# PixelPusher-ethernet-extender-shield.net
KiCad netlist of a schematic drawn in EAGLE
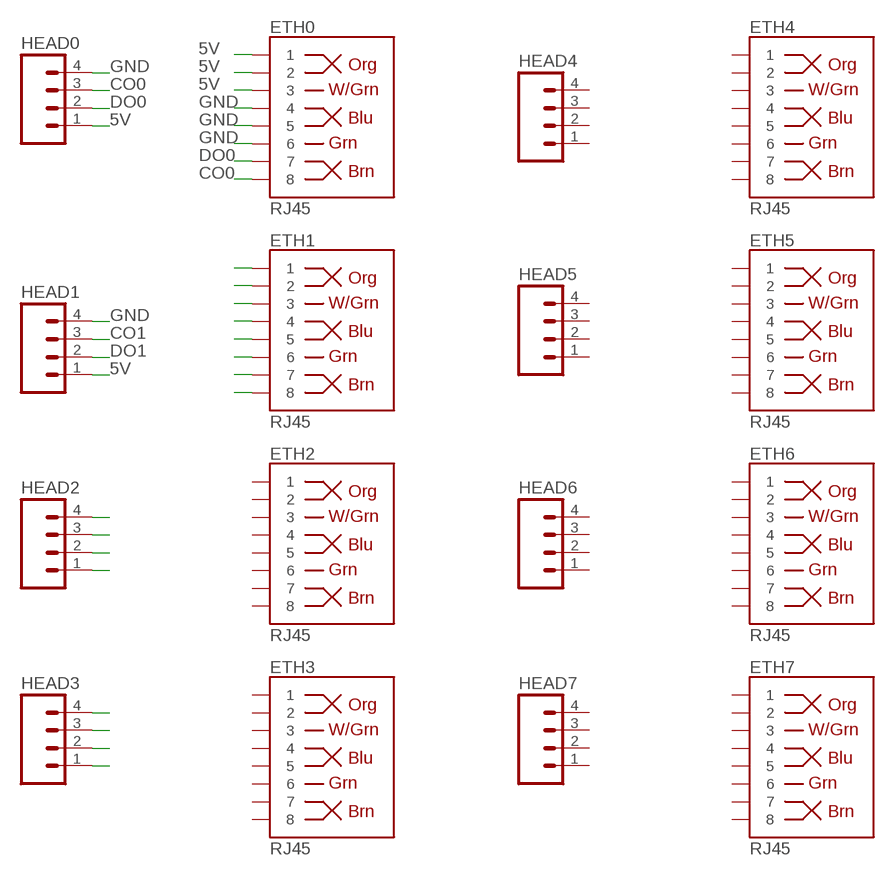
[diagram p0: schematic, sheet 1]

(export (version "E")
  (design (tool "Eeschema 10.0.6"))
  (components
    (comp (ref "ETH0")
      (value "RJ45")
      (footprint "eagle-import:RJ45-8")
      (libsource (lib "eagle-import") (part "RJ45-8PTH"))
    )
    (comp (ref "ETH1")
      (value "RJ45")
      (footprint "eagle-import:RJ45-8")
      (libsource (lib "eagle-import") (part "RJ45-8PTH"))
    )
    (comp (ref "ETH2")
      (value "RJ45")
      (footprint "eagle-import:RJ45-8")
      (libsource (lib "eagle-import") (part "RJ45-8PTH"))
    )
    (comp (ref "ETH3")
      (value "RJ45")
      (footprint "eagle-import:RJ45-8")
      (libsource (lib "eagle-import") (part "RJ45-8PTH"))
    )
    (comp (ref "ETH4")
      (value "RJ45")
      (footprint "eagle-import:RJ45-8")
      (libsource (lib "eagle-import") (part "RJ45-8PTH"))
    )
    (comp (ref "ETH5")
      (value "RJ45")
      (footprint "eagle-import:RJ45-8")
      (libsource (lib "eagle-import") (part "RJ45-8PTH"))
    )
    (comp (ref "ETH6")
      (value "RJ45")
      (footprint "eagle-import:RJ45-8")
      (libsource (lib "eagle-import") (part "RJ45-8PTH"))
    )
    (comp (ref "ETH7")
      (value "RJ45")
      (footprint "eagle-import:RJ45-8")
      (libsource (lib "eagle-import") (part "RJ45-8PTH"))
    )
    (comp (ref "HEAD0")
      (value "M04JST-PTH-VERT")
      (footprint "eagle-import:JST-4-PTH-VERT")
      (libsource (lib "eagle-import") (part "M04JST-PTH-VERT"))
    )
    (comp (ref "HEAD1")
      (value "M04JST-PTH-VERT")
      (footprint "eagle-import:JST-4-PTH-VERT")
      (libsource (lib "eagle-import") (part "M04JST-PTH-VERT"))
    )
    (comp (ref "HEAD2")
      (value "M04JST-PTH-VERT")
      (footprint "eagle-import:JST-4-PTH-VERT")
      (libsource (lib "eagle-import") (part "M04JST-PTH-VERT"))
    )
    (comp (ref "HEAD3")
      (value "M04JST-PTH-VERT")
      (footprint "eagle-import:JST-4-PTH-VERT")
      (libsource (lib "eagle-import") (part "M04JST-PTH-VERT"))
    )
    (comp (ref "HEAD4")
      (value "M04JST-PTH-VERT")
      (footprint "eagle-import:JST-4-PTH-VERT")
      (libsource (lib "eagle-import") (part "M04JST-PTH-VERT"))
    )
    (comp (ref "HEAD5")
      (value "M04JST-PTH-VERT")
      (footprint "eagle-import:JST-4-PTH-VERT")
      (libsource (lib "eagle-import") (part "M04JST-PTH-VERT"))
    )
    (comp (ref "HEAD6")
      (value "M04JST-PTH-VERT")
      (footprint "eagle-import:JST-4-PTH-VERT")
      (libsource (lib "eagle-import") (part "M04JST-PTH-VERT"))
    )
    (comp (ref "HEAD7")
      (value "M04JST-PTH-VERT")
      (footprint "eagle-import:JST-4-PTH-VERT")
      (libsource (lib "eagle-import") (part "M04JST-PTH-VERT"))
    )
  )
  (nets
    (net (code "1") (name "/5V") (class "Default")
      (node (ref "ETH0") (pin "1") (pinfunction "1_1") (pintype "bidirectional"))
      (node (ref "ETH0") (pin "2") (pinfunction "2_2") (pintype "bidirectional"))
      (node (ref "ETH0") (pin "3") (pinfunction "3_3") (pintype "bidirectional"))
      (node (ref "HEAD0") (pin "1") (pinfunction "1_1") (pintype "passive"))
      (node (ref "HEAD1") (pin "1") (pinfunction "1_1") (pintype "passive"))
    )
    (net (code "2") (name "/CO0") (class "Default")
      (node (ref "ETH0") (pin "8") (pinfunction "8_8") (pintype "bidirectional"))
      (node (ref "HEAD0") (pin "3") (pinfunction "3_3") (pintype "passive"))
    )
    (net (code "3") (name "/CO1") (class "Default")
      (node (ref "HEAD1") (pin "3") (pinfunction "3_3") (pintype "passive"))
    )
    (net (code "4") (name "/DO0") (class "Default")
      (node (ref "ETH0") (pin "7") (pinfunction "7_7") (pintype "bidirectional"))
      (node (ref "HEAD0") (pin "2") (pinfunction "2_2") (pintype "passive"))
    )
    (net (code "5") (name "/DO1") (class "Default")
      (node (ref "HEAD1") (pin "2") (pinfunction "2_2") (pintype "passive"))
    )
    (net (code "6") (name "/GND") (class "Default")
      (node (ref "ETH0") (pin "4") (pinfunction "4_4") (pintype "bidirectional"))
      (node (ref "ETH0") (pin "5") (pinfunction "5_5") (pintype "bidirectional"))
      (node (ref "ETH0") (pin "6") (pinfunction "6_6") (pintype "bidirectional"))
      (node (ref "HEAD0") (pin "4") (pinfunction "4_4") (pintype "passive"))
      (node (ref "HEAD1") (pin "4") (pinfunction "4_4") (pintype "passive"))
    )
    (net (code "7") (name "unconnected-(ETH1-Pad1)") (class "Default")
      (node (ref "ETH1") (pin "1") (pinfunction "1_1") (pintype "bidirectional"))
    )
    (net (code "8") (name "unconnected-(ETH1-Pad2)") (class "Default")
      (node (ref "ETH1") (pin "2") (pinfunction "2_2") (pintype "bidirectional"))
    )
    (net (code "9") (name "unconnected-(ETH1-Pad3)") (class "Default")
      (node (ref "ETH1") (pin "3") (pinfunction "3_3") (pintype "bidirectional"))
    )
    (net (code "10") (name "unconnected-(ETH1-Pad4)") (class "Default")
      (node (ref "ETH1") (pin "4") (pinfunction "4_4") (pintype "bidirectional"))
    )
    (net (code "11") (name "unconnected-(ETH1-Pad5)") (class "Default")
      (node (ref "ETH1") (pin "5") (pinfunction "5_5") (pintype "bidirectional"))
    )
    (net (code "12") (name "unconnected-(ETH1-Pad6)") (class "Default")
      (node (ref "ETH1") (pin "6") (pinfunction "6_6") (pintype "bidirectional"))
    )
    (net (code "13") (name "unconnected-(ETH1-Pad7)") (class "Default")
      (node (ref "ETH1") (pin "7") (pinfunction "7_7") (pintype "bidirectional"))
    )
    (net (code "14") (name "unconnected-(ETH1-Pad8)") (class "Default")
      (node (ref "ETH1") (pin "8") (pinfunction "8_8") (pintype "bidirectional"))
    )
    (net (code "15") (name "unconnected-(ETH2-Pad1)") (class "Default")
      (node (ref "ETH2") (pin "1") (pinfunction "1_1") (pintype "bidirectional"))
    )
    (net (code "16") (name "unconnected-(ETH2-Pad2)") (class "Default")
      (node (ref "ETH2") (pin "2") (pinfunction "2_2") (pintype "bidirectional"))
    )
    (net (code "17") (name "unconnected-(ETH2-Pad3)") (class "Default")
      (node (ref "ETH2") (pin "3") (pinfunction "3_3") (pintype "bidirectional"))
    )
    (net (code "18") (name "unconnected-(ETH2-Pad4)") (class "Default")
      (node (ref "ETH2") (pin "4") (pinfunction "4_4") (pintype "bidirectional"))
    )
    (net (code "19") (name "unconnected-(ETH2-Pad5)") (class "Default")
      (node (ref "ETH2") (pin "5") (pinfunction "5_5") (pintype "bidirectional"))
    )
    (net (code "20") (name "unconnected-(ETH2-Pad6)") (class "Default")
      (node (ref "ETH2") (pin "6") (pinfunction "6_6") (pintype "bidirectional"))
    )
    (net (code "21") (name "unconnected-(ETH2-Pad7)") (class "Default")
      (node (ref "ETH2") (pin "7") (pinfunction "7_7") (pintype "bidirectional"))
    )
    (net (code "22") (name "unconnected-(ETH2-Pad8)") (class "Default")
      (node (ref "ETH2") (pin "8") (pinfunction "8_8") (pintype "bidirectional"))
    )
    (net (code "23") (name "unconnected-(ETH3-Pad1)") (class "Default")
      (node (ref "ETH3") (pin "1") (pinfunction "1_1") (pintype "bidirectional"))
    )
    (net (code "24") (name "unconnected-(ETH3-Pad2)") (class "Default")
      (node (ref "ETH3") (pin "2") (pinfunction "2_2") (pintype "bidirectional"))
    )
    (net (code "25") (name "unconnected-(ETH3-Pad3)") (class "Default")
      (node (ref "ETH3") (pin "3") (pinfunction "3_3") (pintype "bidirectional"))
    )
    (net (code "26") (name "unconnected-(ETH3-Pad4)") (class "Default")
      (node (ref "ETH3") (pin "4") (pinfunction "4_4") (pintype "bidirectional"))
    )
    (net (code "27") (name "unconnected-(ETH3-Pad5)") (class "Default")
      (node (ref "ETH3") (pin "5") (pinfunction "5_5") (pintype "bidirectional"))
    )
    (net (code "28") (name "unconnected-(ETH3-Pad6)") (class "Default")
      (node (ref "ETH3") (pin "6") (pinfunction "6_6") (pintype "bidirectional"))
    )
    (net (code "29") (name "unconnected-(ETH3-Pad7)") (class "Default")
      (node (ref "ETH3") (pin "7") (pinfunction "7_7") (pintype "bidirectional"))
    )
    (net (code "30") (name "unconnected-(ETH3-Pad8)") (class "Default")
      (node (ref "ETH3") (pin "8") (pinfunction "8_8") (pintype "bidirectional"))
    )
    (net (code "31") (name "unconnected-(ETH4-Pad1)") (class "Default")
      (node (ref "ETH4") (pin "1") (pinfunction "1_1") (pintype "bidirectional"))
    )
    (net (code "32") (name "unconnected-(ETH4-Pad2)") (class "Default")
      (node (ref "ETH4") (pin "2") (pinfunction "2_2") (pintype "bidirectional"))
    )
    (net (code "33") (name "unconnected-(ETH4-Pad3)") (class "Default")
      (node (ref "ETH4") (pin "3") (pinfunction "3_3") (pintype "bidirectional"))
    )
    (net (code "34") (name "unconnected-(ETH4-Pad4)") (class "Default")
      (node (ref "ETH4") (pin "4") (pinfunction "4_4") (pintype "bidirectional"))
    )
    (net (code "35") (name "unconnected-(ETH4-Pad5)") (class "Default")
      (node (ref "ETH4") (pin "5") (pinfunction "5_5") (pintype "bidirectional"))
    )
    (net (code "36") (name "unconnected-(ETH4-Pad6)") (class "Default")
      (node (ref "ETH4") (pin "6") (pinfunction "6_6") (pintype "bidirectional"))
    )
    (net (code "37") (name "unconnected-(ETH4-Pad7)") (class "Default")
      (node (ref "ETH4") (pin "7") (pinfunction "7_7") (pintype "bidirectional"))
    )
    (net (code "38") (name "unconnected-(ETH4-Pad8)") (class "Default")
      (node (ref "ETH4") (pin "8") (pinfunction "8_8") (pintype "bidirectional"))
    )
    (net (code "39") (name "unconnected-(ETH5-Pad1)") (class "Default")
      (node (ref "ETH5") (pin "1") (pinfunction "1_1") (pintype "bidirectional"))
    )
    (net (code "40") (name "unconnected-(ETH5-Pad2)") (class "Default")
      (node (ref "ETH5") (pin "2") (pinfunction "2_2") (pintype "bidirectional"))
    )
    (net (code "41") (name "unconnected-(ETH5-Pad3)") (class "Default")
      (node (ref "ETH5") (pin "3") (pinfunction "3_3") (pintype "bidirectional"))
    )
    (net (code "42") (name "unconnected-(ETH5-Pad4)") (class "Default")
      (node (ref "ETH5") (pin "4") (pinfunction "4_4") (pintype "bidirectional"))
    )
    (net (code "43") (name "unconnected-(ETH5-Pad5)") (class "Default")
      (node (ref "ETH5") (pin "5") (pinfunction "5_5") (pintype "bidirectional"))
    )
    (net (code "44") (name "unconnected-(ETH5-Pad6)") (class "Default")
      (node (ref "ETH5") (pin "6") (pinfunction "6_6") (pintype "bidirectional"))
    )
    (net (code "45") (name "unconnected-(ETH5-Pad7)") (class "Default")
      (node (ref "ETH5") (pin "7") (pinfunction "7_7") (pintype "bidirectional"))
    )
    (net (code "46") (name "unconnected-(ETH5-Pad8)") (class "Default")
      (node (ref "ETH5") (pin "8") (pinfunction "8_8") (pintype "bidirectional"))
    )
    (net (code "47") (name "unconnected-(ETH6-Pad1)") (class "Default")
      (node (ref "ETH6") (pin "1") (pinfunction "1_1") (pintype "bidirectional"))
    )
    (net (code "48") (name "unconnected-(ETH6-Pad2)") (class "Default")
      (node (ref "ETH6") (pin "2") (pinfunction "2_2") (pintype "bidirectional"))
    )
    (net (code "49") (name "unconnected-(ETH6-Pad3)") (class "Default")
      (node (ref "ETH6") (pin "3") (pinfunction "3_3") (pintype "bidirectional"))
    )
    (net (code "50") (name "unconnected-(ETH6-Pad4)") (class "Default")
      (node (ref "ETH6") (pin "4") (pinfunction "4_4") (pintype "bidirectional"))
    )
    (net (code "51") (name "unconnected-(ETH6-Pad5)") (class "Default")
      (node (ref "ETH6") (pin "5") (pinfunction "5_5") (pintype "bidirectional"))
    )
    (net (code "52") (name "unconnected-(ETH6-Pad6)") (class "Default")
      (node (ref "ETH6") (pin "6") (pinfunction "6_6") (pintype "bidirectional"))
    )
    (net (code "53") (name "unconnected-(ETH6-Pad7)") (class "Default")
      (node (ref "ETH6") (pin "7") (pinfunction "7_7") (pintype "bidirectional"))
    )
    (net (code "54") (name "unconnected-(ETH6-Pad8)") (class "Default")
      (node (ref "ETH6") (pin "8") (pinfunction "8_8") (pintype "bidirectional"))
    )
    (net (code "55") (name "unconnected-(ETH7-Pad1)") (class "Default")
      (node (ref "ETH7") (pin "1") (pinfunction "1_1") (pintype "bidirectional"))
    )
    (net (code "56") (name "unconnected-(ETH7-Pad2)") (class "Default")
      (node (ref "ETH7") (pin "2") (pinfunction "2_2") (pintype "bidirectional"))
    )
    (net (code "57") (name "unconnected-(ETH7-Pad3)") (class "Default")
      (node (ref "ETH7") (pin "3") (pinfunction "3_3") (pintype "bidirectional"))
    )
    (net (code "58") (name "unconnected-(ETH7-Pad4)") (class "Default")
      (node (ref "ETH7") (pin "4") (pinfunction "4_4") (pintype "bidirectional"))
    )
    (net (code "59") (name "unconnected-(ETH7-Pad5)") (class "Default")
      (node (ref "ETH7") (pin "5") (pinfunction "5_5") (pintype "bidirectional"))
    )
    (net (code "60") (name "unconnected-(ETH7-Pad6)") (class "Default")
      (node (ref "ETH7") (pin "6") (pinfunction "6_6") (pintype "bidirectional"))
    )
    (net (code "61") (name "unconnected-(ETH7-Pad7)") (class "Default")
      (node (ref "ETH7") (pin "7") (pinfunction "7_7") (pintype "bidirectional"))
    )
    (net (code "62") (name "unconnected-(ETH7-Pad8)") (class "Default")
      (node (ref "ETH7") (pin "8") (pinfunction "8_8") (pintype "bidirectional"))
    )
    (net (code "63") (name "unconnected-(HEAD2-Pad1)") (class "Default")
      (node (ref "HEAD2") (pin "1") (pinfunction "1_1") (pintype "passive"))
    )
    (net (code "64") (name "unconnected-(HEAD2-Pad2)") (class "Default")
      (node (ref "HEAD2") (pin "2") (pinfunction "2_2") (pintype "passive"))
    )
    (net (code "65") (name "unconnected-(HEAD2-Pad3)") (class "Default")
      (node (ref "HEAD2") (pin "3") (pinfunction "3_3") (pintype "passive"))
    )
    (net (code "66") (name "unconnected-(HEAD2-Pad4)") (class "Default")
      (node (ref "HEAD2") (pin "4") (pinfunction "4_4") (pintype "passive"))
    )
    (net (code "67") (name "unconnected-(HEAD3-Pad1)") (class "Default")
      (node (ref "HEAD3") (pin "1") (pinfunction "1_1") (pintype "passive"))
    )
    (net (code "68") (name "unconnected-(HEAD3-Pad2)") (class "Default")
      (node (ref "HEAD3") (pin "2") (pinfunction "2_2") (pintype "passive"))
    )
    (net (code "69") (name "unconnected-(HEAD3-Pad3)") (class "Default")
      (node (ref "HEAD3") (pin "3") (pinfunction "3_3") (pintype "passive"))
    )
    (net (code "70") (name "unconnected-(HEAD3-Pad4)") (class "Default")
      (node (ref "HEAD3") (pin "4") (pinfunction "4_4") (pintype "passive"))
    )
    (net (code "71") (name "unconnected-(HEAD4-Pad1)") (class "Default")
      (node (ref "HEAD4") (pin "1") (pinfunction "1_1") (pintype "passive"))
    )
    (net (code "72") (name "unconnected-(HEAD4-Pad2)") (class "Default")
      (node (ref "HEAD4") (pin "2") (pinfunction "2_2") (pintype "passive"))
    )
    (net (code "73") (name "unconnected-(HEAD4-Pad3)") (class "Default")
      (node (ref "HEAD4") (pin "3") (pinfunction "3_3") (pintype "passive"))
    )
    (net (code "74") (name "unconnected-(HEAD4-Pad4)") (class "Default")
      (node (ref "HEAD4") (pin "4") (pinfunction "4_4") (pintype "passive"))
    )
    (net (code "75") (name "unconnected-(HEAD5-Pad1)") (class "Default")
      (node (ref "HEAD5") (pin "1") (pinfunction "1_1") (pintype "passive"))
    )
    (net (code "76") (name "unconnected-(HEAD5-Pad2)") (class "Default")
      (node (ref "HEAD5") (pin "2") (pinfunction "2_2") (pintype "passive"))
    )
    (net (code "77") (name "unconnected-(HEAD5-Pad3)") (class "Default")
      (node (ref "HEAD5") (pin "3") (pinfunction "3_3") (pintype "passive"))
    )
    (net (code "78") (name "unconnected-(HEAD5-Pad4)") (class "Default")
      (node (ref "HEAD5") (pin "4") (pinfunction "4_4") (pintype "passive"))
    )
    (net (code "79") (name "unconnected-(HEAD6-Pad1)") (class "Default")
      (node (ref "HEAD6") (pin "1") (pinfunction "1_1") (pintype "passive"))
    )
    (net (code "80") (name "unconnected-(HEAD6-Pad2)") (class "Default")
      (node (ref "HEAD6") (pin "2") (pinfunction "2_2") (pintype "passive"))
    )
    (net (code "81") (name "unconnected-(HEAD6-Pad3)") (class "Default")
      (node (ref "HEAD6") (pin "3") (pinfunction "3_3") (pintype "passive"))
    )
    (net (code "82") (name "unconnected-(HEAD6-Pad4)") (class "Default")
      (node (ref "HEAD6") (pin "4") (pinfunction "4_4") (pintype "passive"))
    )
    (net (code "83") (name "unconnected-(HEAD7-Pad1)") (class "Default")
      (node (ref "HEAD7") (pin "1") (pinfunction "1_1") (pintype "passive"))
    )
    (net (code "84") (name "unconnected-(HEAD7-Pad2)") (class "Default")
      (node (ref "HEAD7") (pin "2") (pinfunction "2_2") (pintype "passive"))
    )
    (net (code "85") (name "unconnected-(HEAD7-Pad3)") (class "Default")
      (node (ref "HEAD7") (pin "3") (pinfunction "3_3") (pintype "passive"))
    )
    (net (code "86") (name "unconnected-(HEAD7-Pad4)") (class "Default")
      (node (ref "HEAD7") (pin "4") (pinfunction "4_4") (pintype "passive"))
    )
  )
)
